# Mosfet_Driver_Circuit.net
KiCad netlist of a schematic drawn in Altium Designer
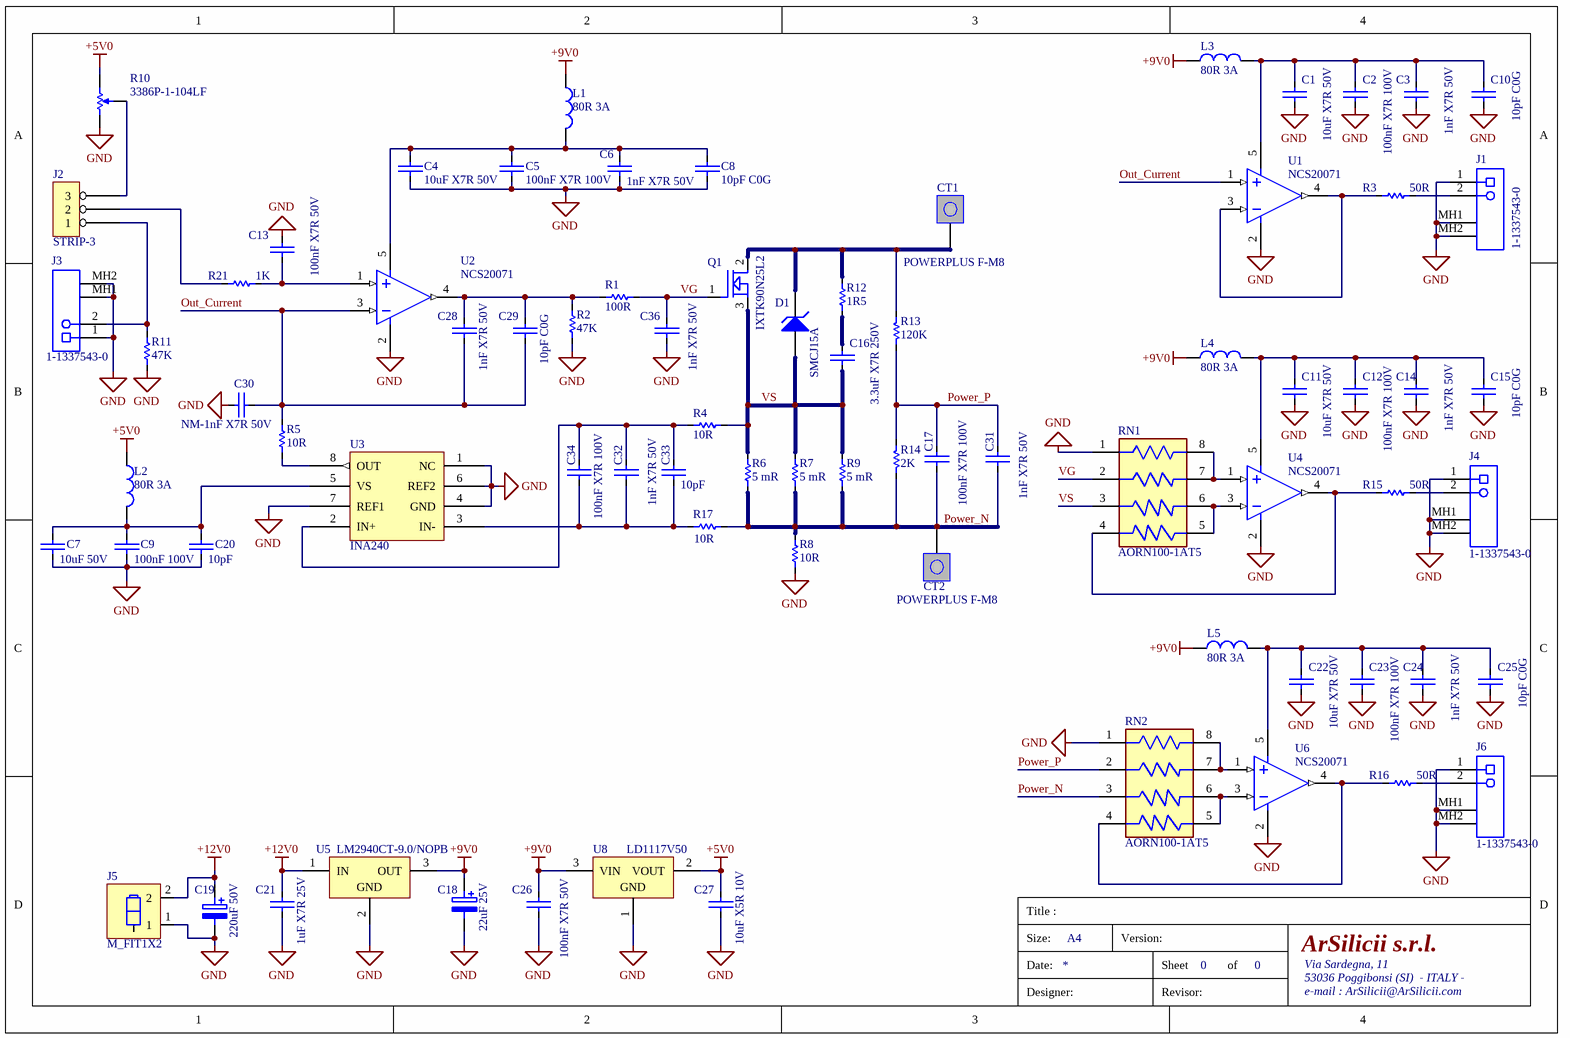
[diagram p0: Mosfet_Driver_Circuit.SchDoc]

(export (version "E")
  (design (tool "Eeschema 10.0.6"))
  (components
    (comp (ref "C1")
      (value "10uF X7R 50V")
      (footprint "1206")
      (description "Capacità")
      (fields
        (field (name "1 SUPPLIER PART NUMBER") "CL31B106KBHNNNE")
        (field (name "ARSILICII PART NUMBER") "CPC0232011")
      )
      (libsource (lib "Library_20-02-20") (part "CAP_10uF X7R 50V_1206"))
    )
    (comp (ref "C2")
      (value "100nF X7R 100V")
      (footprint "0805")
      (description "Capacità")
      (fields
        (field (name "1 SUPPLIER PART NUMBER") "CL21B104KCFSFNG")
        (field (name "2 SUPPLIER PART NUMBER") "1907331")
      )
      (libsource (lib "Library_20-02-20") (part "CAP_100nF X7R 100V_0805"))
    )
    (comp (ref "C3")
      (value "1nF X7R 50V")
      (footprint "0805")
      (description "Capacità")
      (fields
        (field (name "1 SUPPLIER PART NUMBER") "B37941K5102K60")
        (field (name "2 SUPPLIER PART NUMBER") "0805B102K5CT")
      )
      (libsource (lib "Library_20-02-20") (part "CAP_1nF X7R 50V_0805"))
    )
    (comp (ref "C4")
      (value "10uF X7R 50V")
      (footprint "1206")
      (description "Capacità")
      (fields
        (field (name "1 SUPPLIER PART NUMBER") "CL31B106KBHNNNE")
        (field (name "ARSILICII PART NUMBER") "CPC0232011")
      )
      (libsource (lib "Library_20-02-20") (part "CAP_10uF X7R 50V_1206"))
    )
    (comp (ref "C5")
      (value "100nF X7R 100V")
      (footprint "0805")
      (description "Capacità")
      (fields
        (field (name "1 SUPPLIER PART NUMBER") "CL21B104KCFSFNG")
        (field (name "2 SUPPLIER PART NUMBER") "1907331")
      )
      (libsource (lib "Library_20-02-20") (part "CAP_100nF X7R 100V_0805"))
    )
    (comp (ref "C6")
      (value "1nF X7R 50V")
      (footprint "0805")
      (description "Capacità")
      (fields
        (field (name "1 SUPPLIER PART NUMBER") "B37941K5102K60")
        (field (name "2 SUPPLIER PART NUMBER") "0805B102K5CT")
      )
      (libsource (lib "Library_20-02-20") (part "CAP_1nF X7R 50V_0805"))
    )
    (comp (ref "C7")
      (value "10uF 50V")
      (footprint "1206")
      (description "Capacità")
      (fields
        (field (name "1 SUPPLIER PART NUMBER") "CL31B106KBHNNNE")
        (field (name "ARSILICII PART NUMBER") "CPC0232011")
      )
      (libsource (lib "Library_20-02-20") (part "CAP_10uF X7R 50V_1206"))
    )
    (comp (ref "C8")
      (value "10pF C0G")
      (footprint "0805")
      (description "Capacità")
      (fields (field (name "ARSILICII PART NUMBER") "CPC0614010"))
      (libsource (lib "Library_20-02-20") (part "CAP_10pF C0G_0805"))
    )
    (comp (ref "C9")
      (value "100nF 100V")
      (footprint "0805")
      (description "Capacità")
      (fields
        (field (name "1 SUPPLIER PART NUMBER") "CL21B104KCFSFNG")
        (field (name "2 SUPPLIER PART NUMBER") "1907331")
      )
      (libsource (lib "Library_20-02-20") (part "CAP_100nF X7R 100V_0805"))
    )
    (comp (ref "C10")
      (value "10pF C0G")
      (footprint "0805")
      (description "Capacità")
      (fields (field (name "ARSILICII PART NUMBER") "CPC0614010"))
      (libsource (lib "Library_20-02-20") (part "CAP_10pF C0G_0805"))
    )
    (comp (ref "C11")
      (value "10uF X7R 50V")
      (footprint "1206")
      (description "Capacità")
      (fields
        (field (name "1 SUPPLIER PART NUMBER") "CL31B106KBHNNNE")
        (field (name "ARSILICII PART NUMBER") "CPC0232011")
      )
      (libsource (lib "Library_20-02-20") (part "CAP_10uF X7R 50V_1206"))
    )
    (comp (ref "C12")
      (value "100nF X7R 100V")
      (footprint "0805")
      (description "Capacità")
      (fields
        (field (name "1 SUPPLIER PART NUMBER") "CL21B104KCFSFNG")
        (field (name "2 SUPPLIER PART NUMBER") "1907331")
      )
      (libsource (lib "Library_20-02-20") (part "CAP_100nF X7R 100V_0805"))
    )
    (comp (ref "C13")
      (value "100nF X7R 50V")
      (footprint "0805")
      (description "Capacità")
      (fields
        (field (name "1 SUPPLIER PART NUMBER") "C0805C104K5RAC7800")
        (field (name "2 SUPPLIER PART NUMBER") "08055C104KAT2A AVX")
      )
      (libsource (lib "Library_20-02-20") (part "CAP_100nF X7R 50V_0805"))
    )
    (comp (ref "C14")
      (value "1nF X7R 50V")
      (footprint "0805")
      (description "Capacità")
      (fields
        (field (name "1 SUPPLIER PART NUMBER") "B37941K5102K60")
        (field (name "2 SUPPLIER PART NUMBER") "0805B102K5CT")
      )
      (libsource (lib "Library_20-02-20") (part "CAP_1nF X7R 50V_0805"))
    )
    (comp (ref "C15")
      (value "10pF C0G")
      (footprint "0805")
      (description "Capacità")
      (fields (field (name "ARSILICII PART NUMBER") "CPC0614010"))
      (libsource (lib "Library_20-02-20") (part "CAP_10pF C0G_0805"))
    )
    (comp (ref "C16")
      (value "3.3uF X7R 250V")
      (footprint "2220")
      (description "Capacità")
      (fields
        (field (name "1 SUPPLIER PART NUMBER") "2435506")
        (field (name "2 SUPPLIER PART NUMBER") "810-CGA9N3X7R2E105K")
      )
      (libsource (lib "Library_20-02-20") (part "CAP_1uF X7R 250V_2220"))
    )
    (comp (ref "C17")
      (value "100nF X7R 100V")
      (footprint "0805")
      (description "Capacità")
      (fields
        (field (name "1 SUPPLIER PART NUMBER") "CL21B104KCFSFNG")
        (field (name "2 SUPPLIER PART NUMBER") "1907331")
      )
      (libsource (lib "Library_20-02-20") (part "CAP_100nF X7R 100V_0805"))
    )
    (comp (ref "C18")
      (value "22uF 25V")
      (footprint "TANT_D")
      (description "Capacità polarizzata")
      (fields
        (field (name "1 SUPPLIER PART NUMBER") "KETT491D226K025AT")
        (field (name "ARSILICII PART NUMBER") "CPC0352022")
      )
      (libsource (lib "Library_20-02-20") (part "CAP_TANT_22uF 25V Case D"))
    )
    (comp (ref "C19")
      (value "220uF 50V")
      (footprint "C_G55")
      (description "Capacità polarizzata")
      (fields
        (field (name "2 SUPPLIER PART NUMBER") "5194346")
        (field (name "ARSILICII PART NUMBER") "CPC0402221")
      )
      (libsource (lib "Library_20-02-20") (part "CAP_EL_220uF 50V"))
    )
    (comp (ref "C20")
      (value "10pF")
      (footprint "0805")
      (description "Capacità")
      (fields (field (name "ARSILICII PART NUMBER") "CPC0614010"))
      (libsource (lib "Library_20-02-20") (part "CAP_10pF C0G_0805"))
    )
    (comp (ref "C21")
      (value "1uF X7R 25V")
      (footprint "0805")
      (description "Capacità")
      (fields
        (field (name "1 SUPPLIER PART NUMBER") "CL21B105KAFNNNG")
        (field (name "ARSILICII PART NUMBER") "CPC0212002")
      )
      (libsource (lib "Library_20-02-20") (part "CAP_1uF X7R 25V_0805"))
    )
    (comp (ref "C22")
      (value "10uF X7R 50V")
      (footprint "1206")
      (description "Capacità")
      (fields
        (field (name "1 SUPPLIER PART NUMBER") "CL31B106KBHNNNE")
        (field (name "ARSILICII PART NUMBER") "CPC0232011")
      )
      (libsource (lib "Library_20-02-20") (part "CAP_10uF X7R 50V_1206"))
    )
    (comp (ref "C23")
      (value "100nF X7R 100V")
      (footprint "0805")
      (description "Capacità")
      (fields
        (field (name "1 SUPPLIER PART NUMBER") "CL21B104KCFSFNG")
        (field (name "2 SUPPLIER PART NUMBER") "1907331")
      )
      (libsource (lib "Library_20-02-20") (part "CAP_100nF X7R 100V_0805"))
    )
    (comp (ref "C24")
      (value "1nF X7R 50V")
      (footprint "0805")
      (description "Capacità")
      (fields
        (field (name "1 SUPPLIER PART NUMBER") "B37941K5102K60")
        (field (name "2 SUPPLIER PART NUMBER") "0805B102K5CT")
      )
      (libsource (lib "Library_20-02-20") (part "CAP_1nF X7R 50V_0805"))
    )
    (comp (ref "C25")
      (value "10pF C0G")
      (footprint "0805")
      (description "Capacità")
      (fields (field (name "ARSILICII PART NUMBER") "CPC0614010"))
      (libsource (lib "Library_20-02-20") (part "CAP_10pF C0G_0805"))
    )
    (comp (ref "C26")
      (value "100nF X7R 50V")
      (footprint "0805")
      (description "Capacità")
      (fields
        (field (name "1 SUPPLIER PART NUMBER") "C0805C104K5RAC7800")
        (field (name "2 SUPPLIER PART NUMBER") "08055C104KAT2A AVX")
      )
      (libsource (lib "Library_20-02-20") (part "CAP_100nF X7R 50V_0805"))
    )
    (comp (ref "C27")
      (value "10uF X5R 10V")
      (footprint "0805")
      (description "Capacità")
      (fields
        (field (name "1 SUPPLIER PART NUMBER") "CL21A106KPFNNNE")
        (field (name "ARSILICII PART NUMBER") "CPC0212010")
      )
      (libsource (lib "Library_20-02-20") (part "CAP_10uF X5R 10V_0805"))
    )
    (comp (ref "C28")
      (value "1nF X7R 50V")
      (footprint "0805")
      (description "Capacità")
      (fields
        (field (name "1 SUPPLIER PART NUMBER") "B37941K5102K60")
        (field (name "2 SUPPLIER PART NUMBER") "0805B102K5CT")
      )
      (libsource (lib "Library_20-02-20") (part "CAP_1nF X7R 50V_0805"))
    )
    (comp (ref "C29")
      (value "10pF C0G")
      (footprint "0805")
      (description "Capacità")
      (fields (field (name "ARSILICII PART NUMBER") "CPC0614010"))
      (libsource (lib "Library_20-02-20") (part "CAP_10pF C0G_0805"))
    )
    (comp (ref "C30")
      (value "NM-1nF X7R 50V")
      (footprint "0805")
      (description "Capacità")
      (fields
        (field (name "1 SUPPLIER PART NUMBER") "B37941K5102K60")
        (field (name "2 SUPPLIER PART NUMBER") "0805B102K5CT")
      )
      (libsource (lib "Library_20-02-20") (part "CAP_1nF X7R 50V_0805"))
    )
    (comp (ref "C31")
      (value "1nF X7R 50V")
      (footprint "0805")
      (description "Capacità")
      (fields
        (field (name "1 SUPPLIER PART NUMBER") "B37941K5102K60")
        (field (name "2 SUPPLIER PART NUMBER") "0805B102K5CT")
      )
      (libsource (lib "Library_20-02-20") (part "CAP_1nF X7R 50V_0805"))
    )
    (comp (ref "C32")
      (value "1nF X7R 50V")
      (footprint "0805")
      (description "Capacità")
      (fields
        (field (name "1 SUPPLIER PART NUMBER") "B37941K5102K60")
        (field (name "2 SUPPLIER PART NUMBER") "0805B102K5CT")
      )
      (libsource (lib "Library_20-02-20") (part "CAP_1nF X7R 50V_0805"))
    )
    (comp (ref "C33")
      (value "10pF")
      (footprint "0805")
      (description "Capacità")
      (fields (field (name "ARSILICII PART NUMBER") "CPC0614010"))
      (libsource (lib "Library_20-02-20") (part "CAP_10pF C0G_0805"))
    )
    (comp (ref "C34")
      (value "100nF X7R 100V")
      (footprint "0805")
      (description "Capacità")
      (fields
        (field (name "1 SUPPLIER PART NUMBER") "CL21B104KCFSFNG")
        (field (name "2 SUPPLIER PART NUMBER") "1907331")
      )
      (libsource (lib "ArS_Library") (part "CAP_100nF X7R 100V_0805"))
    )
    (comp (ref "C36")
      (value "1nF X7R 50V")
      (footprint "0805")
      (description "Capacità")
      (fields
        (field (name "1 SUPPLIER PART NUMBER") "B37941K5102K60")
        (field (name "2 SUPPLIER PART NUMBER") "0805B102K5CT")
      )
      (libsource (lib "Library_20-02-20") (part "CAP_1nF X7R 50V_0805"))
    )
    (comp (ref "CT1")
      (value "POWERPLUS F-M8")
      (footprint "PowerPlus M8")
      (description "Singolo contatto")
      (fields
        (field (name "1 SUPPLIER PART NUMBER") "S98978")
        (field (name "ARSILICII PART NUMBER") "QC04000180")
      )
      (libsource (lib "Library_20-02-20") (part "PAD_POWERPLUS F-M8"))
    )
    (comp (ref "CT2")
      (value "POWERPLUS F-M8")
      (footprint "PowerPlus M8")
      (description "Singolo contatto")
      (fields
        (field (name "1 SUPPLIER PART NUMBER") "S98978")
        (field (name "ARSILICII PART NUMBER") "QC04000180")
      )
      (libsource (lib "") (part "PAD_POWERPLUS F-M8_1"))
    )
    (comp (ref "D1")
      (value "SMCJ15A")
      (footprint "LFUS-DO-214AB-2_V")
      (fields (field (name "MANUFACTURER") "Littelfuse"))
      (libsource (lib "Altium Content Vault") (part "DZEN-AK-2"))
    )
    (comp (ref "J1")
      (value "1-1337543-0")
      (footprint "TECO-1-1337543-0_V")
      (fields (field (name "MANUFACTURER") "TE Connectivity"))
      (libsource (lib "Altium Content Vault") (part "CN-1P-F-R2_A"))
    )
    (comp (ref "J2")
      (value "STRIP-3")
      (footprint "SIP-3")
      (libsource (lib "Library_20-02-20") (part "HEADER 3"))
    )
    (comp (ref "J3")
      (value "1-1337543-0")
      (footprint "TECO-1-1337543-0_V")
      (fields (field (name "MANUFACTURER") "TE Connectivity"))
      (libsource (lib "") (part "CN-1P-F-R2_A_1"))
    )
    (comp (ref "J4")
      (value "1-1337543-0")
      (footprint "TECO-1-1337543-0_V")
      (fields (field (name "MANUFACTURER") "TE Connectivity"))
      (libsource (lib "Altium Content Vault") (part "CN-1P-F-R2_A"))
    )
    (comp (ref "J5")
      (value "M_FIT1X2")
      (footprint "M_FIT_JR1X2V")
      (description "Mini Fit Junior 2 poli")
      (fields (field (name "ARSILICII PART NUMBER") "QA02006000") (field (name "MANUFACTURER") "Molex"))
      (libsource (lib "Library_20-02-20") (part "M_FIT1X2"))
    )
    (comp (ref "J6")
      (value "1-1337543-0")
      (footprint "TECO-1-1337543-0_V")
      (fields (field (name "MANUFACTURER") "TE Connectivity"))
      (libsource (lib "Altium Content Vault") (part "CN-1P-F-R2_A"))
    )
    (comp (ref "L1")
      (value "80R 3A")
      (footprint "1206")
      (description "Ferrite")
      (fields
        (field (name "1 SUPPLIER PART NUMBER") "3275550P")
        (field (name "ARSILICII PART NUMBER") "CPF0006000")
      )
      (libsource (lib "Library_20-02-20") (part "Ferrite 80R 3A"))
    )
    (comp (ref "L2")
      (value "80R 3A")
      (footprint "1206")
      (description "Ferrite")
      (fields
        (field (name "1 SUPPLIER PART NUMBER") "3275550P")
        (field (name "ARSILICII PART NUMBER") "CPF0006000")
      )
      (libsource (lib "Library_20-02-20") (part "Ferrite 80R 3A"))
    )
    (comp (ref "L3")
      (value "80R 3A")
      (footprint "1206")
      (description "Ferrite")
      (fields
        (field (name "1 SUPPLIER PART NUMBER") "3275550P")
        (field (name "ARSILICII PART NUMBER") "CPF0006000")
      )
      (libsource (lib "Library_20-02-20") (part "Ferrite 80R 3A"))
    )
    (comp (ref "L4")
      (value "80R 3A")
      (footprint "1206")
      (description "Ferrite")
      (fields
        (field (name "1 SUPPLIER PART NUMBER") "3275550P")
        (field (name "ARSILICII PART NUMBER") "CPF0006000")
      )
      (libsource (lib "Library_20-02-20") (part "Ferrite 80R 3A"))
    )
    (comp (ref "L5")
      (value "80R 3A")
      (footprint "1206")
      (description "Ferrite")
      (fields
        (field (name "1 SUPPLIER PART NUMBER") "3275550P")
        (field (name "ARSILICII PART NUMBER") "CPF0006000")
      )
      (libsource (lib "Library_20-02-20") (part "Ferrite 80R 3A"))
    )
    (comp (ref "Q1")
      (value "IXTK90N25L2")
      (footprint "Library_20-02-20:TO-247")
      (description "MOS CANALE N-250V-90A Linear")
      (fields
        (field (name "1 SUPPLIER PART NUMBER") "PB90N06S4-04")
        (field (name "2 SUPPLIER PART NUMBER") "826-9042P")
      )
      (libsource (lib "Library_20-02-20") (part "IXTK90N25L2"))
    )
    (comp (ref "R1")
      (value "100R")
      (footprint "0805")
      (description "Resistenza")
      (libsource (lib "Library_20-02-20") (part "RES_SMD"))
    )
    (comp (ref "R2")
      (value "47K")
      (footprint "0805")
      (description "Resistenza")
      (libsource (lib "Library_20-02-20") (part "RES_SMD"))
    )
    (comp (ref "R3")
      (value "50R")
      (footprint "0805")
      (description "Resistenza")
      (libsource (lib "Library_20-02-20") (part "RES_SMD"))
    )
    (comp (ref "R4")
      (value "10R")
      (footprint "0805")
      (description "Resistenza")
      (libsource (lib "Library_20-02-20") (part "RES_SMD"))
    )
    (comp (ref "R5")
      (value "10R")
      (footprint "0805")
      (description "Resistenza")
      (libsource (lib "Library_20-02-20") (part "RES_SMD"))
    )
    (comp (ref "R6")
      (value "5 mR")
      (footprint "2512")
      (description "Resistenza")
      (libsource (lib "Library_20-02-20") (part "RES_SMD"))
    )
    (comp (ref "R7")
      (value "5 mR")
      (footprint "2512")
      (description "Resistenza")
      (libsource (lib "Library_20-02-20") (part "RES_SMD"))
    )
    (comp (ref "R8")
      (value "10R")
      (footprint "1206")
      (description "Resistenza")
      (libsource (lib "Library_20-02-20") (part "RES_SMD"))
    )
    (comp (ref "R9")
      (value "5 mR")
      (footprint "2512")
      (description "Resistenza")
      (libsource (lib "Library_20-02-20") (part "RES_SMD"))
    )
    (comp (ref "R10")
      (value "3386P-1-104LF")
      (footprint "BOUR-3386P")
      (fields (field (name "TOLERANCE") "10%") (field (name "MANUFACTURER") "Bourns"))
      (libsource (lib "Altium Content Vault") (part "RES-ADJ-3_A"))
    )
    (comp (ref "R11")
      (value "47K")
      (footprint "0805")
      (description "Resistenza")
      (libsource (lib "Library_20-02-20") (part "RES_SMD"))
    )
    (comp (ref "R12")
      (value "1R5")
      (footprint "2512")
      (description "Resistenza")
      (libsource (lib "Library_20-02-20") (part "RES_SMD"))
    )
    (comp (ref "R13")
      (value "120K")
      (footprint "2512")
      (description "Resistenza")
      (libsource (lib "Library_20-02-20") (part "RES_SMD"))
    )
    (comp (ref "R14")
      (value "2K")
      (footprint "2512")
      (description "Resistenza")
      (libsource (lib "Library_20-02-20") (part "RES_SMD"))
    )
    (comp (ref "R15")
      (value "50R")
      (footprint "0805")
      (description "Resistenza")
      (libsource (lib "Library_20-02-20") (part "RES_SMD"))
    )
    (comp (ref "R16")
      (value "50R")
      (footprint "0805")
      (description "Resistenza")
      (libsource (lib "Library_20-02-20") (part "RES_SMD"))
    )
    (comp (ref "R17")
      (value "10R")
      (footprint "0805")
      (description "Resistenza")
      (libsource (lib "Library_20-02-20") (part "RES_SMD"))
    )
    (comp (ref "R21")
      (value "1K")
      (footprint "0805")
      (description "Resistenza")
      (libsource (lib "Library_20-02-20") (part "RES_SMD"))
    )
    (comp (ref "RN1")
      (value "AORN100-1AT5")
      (footprint "FP-AORN100-1AT5-IPC_C")
      (description "RES NETWORK 4 RES MULT OHM 8SOIC")
      (fields (field (name "MANUFACTURER") "Vishay") (field (name "TOLERANCE") "0.1%"))
      (libsource (lib "Altium Content Vault") (part "8441eaa576eb2593bca60d5301712c1"))
    )
    (comp (ref "RN2")
      (value "AORN100-1AT5")
      (footprint "FP-AORN100-1AT5-IPC_C")
      (description "RES NETWORK 4 RES MULT OHM 8SOIC")
      (fields (field (name "MANUFACTURER") "Vishay") (field (name "TOLERANCE") "0.1%"))
      (libsource (lib "Altium Content Vault") (part "8441eaa576eb2593bca60d5301712c1"))
    )
    (comp (ref "U1")
      (value "NCS20071")
      (footprint "SOT-553-5")
      (description "Rail-to-Rail Input/Output, 3 MHz Op Amps")
      (fields
        (field (name "1 SUPPLIER PART NUMBER") "MCP6021-E/SN-ND")
        (field (name "MANUFACTURER") "Microchip Technology")
      )
      (libsource (lib "Library_20-02-20") (part "NCS20071"))
    )
    (comp (ref "U2")
      (value "NCS20071")
      (footprint "SOT-553-5")
      (description "Rail-to-Rail Input/Output, 3 MHz Op Amps")
      (fields
        (field (name "1 SUPPLIER PART NUMBER") "MCP6021-E/SN-ND")
        (field (name "MANUFACTURER") "Microchip Technology")
      )
      (libsource (lib "Library_20-02-20") (part "NCS20071"))
    )
    (comp (ref "U3")
      (value "INA240")
      (footprint "TSSOP-8")
      (description "Current sense amplifier")
      (libsource (lib "Library_20-02-20") (part "INA240"))
    )
    (comp (ref "U4")
      (value "NCS20071")
      (footprint "SOT-553-5")
      (description "Rail-to-Rail Input/Output, 3 MHz Op Amps")
      (fields
        (field (name "1 SUPPLIER PART NUMBER") "MCP6021-E/SN-ND")
        (field (name "MANUFACTURER") "Microchip Technology")
      )
      (libsource (lib "Library_20-02-20") (part "NCS20071"))
    )
    (comp (ref "U5")
      (value "LM2940CT-9.0/NOPB")
      (footprint "NDE0003A")
      (description "1A Low Dropout Regulator, 3-pin TO-220, Pb-Free")
      (fields (field (name "MANUFACTURER") "Texas Instruments"))
      (libsource (lib "Altium Content Vault") (part "PM-REG-LM2940-SIL3"))
    )
    (comp (ref "U6")
      (value "NCS20071")
      (footprint "SOT-553-5")
      (description "Rail-to-Rail Input/Output, 3 MHz Op Amps")
      (fields
        (field (name "1 SUPPLIER PART NUMBER") "MCP6021-E/SN-ND")
        (field (name "MANUFACTURER") "Microchip Technology")
      )
      (libsource (lib "Library_20-02-20") (part "NCS20071"))
    )
    (comp (ref "U8")
      (value "LD1117V50")
      (footprint "TO220")
      (description "Fixed Low Drop Positive Voltage Regulator, 5V, 3-Pin TO-220")
      (libsource (lib "Altium Content Vault") (part "PM-REG-LD1117V-SIL3"))
    )
  )
  (nets
    (net (code "1") (name "+5V0") (class "Default")
      (node (ref "C27") (pin "1") (pintype "passive"))
      (node (ref "L2") (pin "1") (pinfunction "1_1") (pintype "passive"))
      (node (ref "R10") (pin "3") (pinfunction "3_3") (pintype "passive"))
      (node (ref "U8") (pin "2") (pinfunction "VOUT_2") (pintype "power_in"))
    )
    (net (code "2") (name "+9V0") (class "Default")
      (node (ref "C18") (pin "1") (pintype "passive"))
      (node (ref "C26") (pin "1") (pintype "passive"))
      (node (ref "L1") (pin "1") (pinfunction "1_1") (pintype "passive"))
      (node (ref "L3") (pin "1") (pinfunction "1_1") (pintype "passive"))
      (node (ref "L4") (pin "1") (pinfunction "1_1") (pintype "passive"))
      (node (ref "L5") (pin "1") (pinfunction "1_1") (pintype "passive"))
      (node (ref "U5") (pin "3") (pinfunction "OUT_3") (pintype "power_in"))
      (node (ref "U8") (pin "3") (pinfunction "VIN_3") (pintype "power_in"))
    )
    (net (code "3") (name "+12V0") (class "Default")
      (node (ref "C19") (pin "1") (pintype "passive"))
      (node (ref "C21") (pin "1") (pintype "passive"))
      (node (ref "J5") (pin "2") (pinfunction "2_2") (pintype "passive"))
      (node (ref "U5") (pin "1") (pinfunction "IN_1") (pintype "power_in"))
    )
    (net (code "4") (name "/Out_Current") (class "Default")
      (node (ref "C28") (pin "2") (pintype "passive"))
      (node (ref "C29") (pin "2") (pintype "passive"))
      (node (ref "C30") (pin "2") (pintype "passive"))
      (node (ref "R5") (pin "2") (pinfunction "2_2") (pintype "passive"))
      (node (ref "U1") (pin "1") (pintype "input"))
      (node (ref "U2") (pin "3") (pintype "input"))
    )
    (net (code "5") (name "/Power_N") (class "Default")
      (node (ref "C17") (pin "2") (pintype "passive"))
      (node (ref "C31") (pin "2") (pintype "passive"))
      (node (ref "CT2") (pin "1") (pinfunction "1_1") (pintype "passive"))
      (node (ref "R14") (pin "2") (pinfunction "2_2") (pintype "passive"))
      (node (ref "R17") (pin "2") (pinfunction "2_2") (pintype "passive"))
      (node (ref "R6") (pin "2") (pinfunction "2_2") (pintype "passive"))
      (node (ref "R7") (pin "2") (pinfunction "2_2") (pintype "passive"))
      (node (ref "R8") (pin "1") (pinfunction "1_1") (pintype "passive"))
      (node (ref "R9") (pin "2") (pinfunction "2_2") (pintype "passive"))
      (node (ref "RN2") (pin "3") (pinfunction "3_3") (pintype "passive"))
    )
    (net (code "6") (name "/Power_P") (class "Default")
      (node (ref "C17") (pin "1") (pintype "passive"))
      (node (ref "C31") (pin "1") (pintype "passive"))
      (node (ref "R13") (pin "2") (pinfunction "2_2") (pintype "passive"))
      (node (ref "R14") (pin "1") (pinfunction "1_1") (pintype "passive"))
      (node (ref "RN2") (pin "2") (pinfunction "2_2") (pintype "passive"))
    )
    (net (code "7") (name "/VG") (class "Default")
      (node (ref "C36") (pin "1") (pintype "passive"))
      (node (ref "Q1") (pin "1") (pinfunction "GATE_1") (pintype "passive"))
      (node (ref "R1") (pin "2") (pinfunction "2_2") (pintype "passive"))
      (node (ref "RN1") (pin "2") (pinfunction "2_2") (pintype "passive"))
    )
    (net (code "8") (name "/VS") (class "Default")
      (node (ref "C16") (pin "2") (pintype "passive"))
      (node (ref "D1") (pin "1") (pinfunction "A_1") (pintype "passive"))
      (node (ref "Q1") (pin "3") (pinfunction "SOURCE_3") (pintype "passive"))
      (node (ref "R4") (pin "2") (pinfunction "2_2") (pintype "passive"))
      (node (ref "R6") (pin "1") (pinfunction "1_1") (pintype "passive"))
      (node (ref "R7") (pin "1") (pinfunction "1_1") (pintype "passive"))
      (node (ref "R9") (pin "1") (pinfunction "1_1") (pintype "passive"))
      (node (ref "RN1") (pin "3") (pinfunction "3_3") (pintype "passive"))
    )
    (net (code "9") (name "GND") (class "Default")
      (node (ref "C1") (pin "2") (pintype "passive"))
      (node (ref "C10") (pin "2") (pintype "passive"))
      (node (ref "C11") (pin "2") (pintype "passive"))
      (node (ref "C12") (pin "2") (pintype "passive"))
      (node (ref "C13") (pin "1") (pintype "passive"))
      (node (ref "C14") (pin "2") (pintype "passive"))
      (node (ref "C15") (pin "2") (pintype "passive"))
      (node (ref "C18") (pin "2") (pintype "passive"))
      (node (ref "C19") (pin "2") (pintype "passive"))
      (node (ref "C2") (pin "2") (pintype "passive"))
      (node (ref "C20") (pin "2") (pintype "passive"))
      (node (ref "C21") (pin "2") (pintype "passive"))
      (node (ref "C22") (pin "2") (pintype "passive"))
      (node (ref "C23") (pin "2") (pintype "passive"))
      (node (ref "C24") (pin "2") (pintype "passive"))
      (node (ref "C25") (pin "2") (pintype "passive"))
      (node (ref "C26") (pin "2") (pintype "passive"))
      (node (ref "C27") (pin "2") (pintype "passive"))
      (node (ref "C3") (pin "2") (pintype "passive"))
      (node (ref "C30") (pin "1") (pintype "passive"))
      (node (ref "C36") (pin "2") (pintype "passive"))
      (node (ref "C4") (pin "2") (pintype "passive"))
      (node (ref "C5") (pin "2") (pintype "passive"))
      (node (ref "C6") (pin "2") (pintype "passive"))
      (node (ref "C7") (pin "2") (pintype "passive"))
      (node (ref "C8") (pin "2") (pintype "passive"))
      (node (ref "C9") (pin "2") (pintype "passive"))
      (node (ref "J1") (pin "1") (pinfunction "1_1") (pintype "passive"))
      (node (ref "J1") (pin "MH1") (pinfunction "MH1_MH1") (pintype "passive"))
      (node (ref "J1") (pin "MH2") (pinfunction "MH2_MH2") (pintype "passive"))
      (node (ref "J3") (pin "1") (pinfunction "1_1") (pintype "passive"))
      (node (ref "J3") (pin "MH1") (pinfunction "MH1_MH1") (pintype "passive"))
      (node (ref "J3") (pin "MH2") (pinfunction "MH2_MH2") (pintype "passive"))
      (node (ref "J4") (pin "1") (pinfunction "1_1") (pintype "passive"))
      (node (ref "J4") (pin "MH1") (pinfunction "MH1_MH1") (pintype "passive"))
      (node (ref "J4") (pin "MH2") (pinfunction "MH2_MH2") (pintype "passive"))
      (node (ref "J5") (pin "1") (pinfunction "1_1") (pintype "passive"))
      (node (ref "J6") (pin "1") (pinfunction "1_1") (pintype "passive"))
      (node (ref "J6") (pin "MH1") (pinfunction "MH1_MH1") (pintype "passive"))
      (node (ref "J6") (pin "MH2") (pinfunction "MH2_MH2") (pintype "passive"))
      (node (ref "R10") (pin "1") (pinfunction "1_1") (pintype "passive"))
      (node (ref "R11") (pin "1") (pinfunction "1_1") (pintype "passive"))
      (node (ref "R2") (pin "2") (pinfunction "2_2") (pintype "passive"))
      (node (ref "R8") (pin "2") (pinfunction "2_2") (pintype "passive"))
      (node (ref "RN1") (pin "1") (pinfunction "1_1") (pintype "passive"))
      (node (ref "RN2") (pin "1") (pinfunction "1_1") (pintype "passive"))
      (node (ref "U1") (pin "2") (pintype "power_in"))
      (node (ref "U2") (pin "2") (pintype "power_in"))
      (node (ref "U3") (pin "1") (pinfunction "NC_1") (pintype "passive"))
      (node (ref "U3") (pin "4") (pinfunction "GND_4") (pintype "power_in"))
      (node (ref "U3") (pin "6") (pinfunction "REF2_6") (pintype "passive"))
      (node (ref "U3") (pin "7") (pinfunction "REF1_7") (pintype "passive"))
      (node (ref "U4") (pin "2") (pintype "power_in"))
      (node (ref "U5") (pin "2") (pinfunction "GND_2") (pintype "power_in"))
      (node (ref "U6") (pin "2") (pintype "power_in"))
      (node (ref "U8") (pin "1") (pinfunction "GND_1") (pintype "power_in"))
    )
    (net (code "10") (name "Net-(C1-Pad1)") (class "Default")
      (node (ref "C1") (pin "1") (pintype "passive"))
      (node (ref "C10") (pin "1") (pintype "passive"))
      (node (ref "C2") (pin "1") (pintype "passive"))
      (node (ref "C3") (pin "1") (pintype "passive"))
      (node (ref "L3") (pin "2") (pinfunction "2_2") (pintype "passive"))
      (node (ref "U1") (pin "5") (pintype "power_in"))
    )
    (net (code "11") (name "Net-(C4-Pad1)") (class "Default")
      (node (ref "C4") (pin "1") (pintype "passive"))
      (node (ref "C5") (pin "1") (pintype "passive"))
      (node (ref "C6") (pin "1") (pintype "passive"))
      (node (ref "C8") (pin "1") (pintype "passive"))
      (node (ref "L1") (pin "2") (pinfunction "2_2") (pintype "passive"))
      (node (ref "U2") (pin "5") (pintype "power_in"))
    )
    (net (code "12") (name "Net-(C11-Pad1)") (class "Default")
      (node (ref "C11") (pin "1") (pintype "passive"))
      (node (ref "C12") (pin "1") (pintype "passive"))
      (node (ref "C14") (pin "1") (pintype "passive"))
      (node (ref "C15") (pin "1") (pintype "passive"))
      (node (ref "L4") (pin "2") (pinfunction "2_2") (pintype "passive"))
      (node (ref "U4") (pin "5") (pintype "power_in"))
    )
    (net (code "13") (name "Net-(C13-Pad2)") (class "Default")
      (node (ref "C13") (pin "2") (pintype "passive"))
      (node (ref "R21") (pin "2") (pinfunction "2_2") (pintype "passive"))
      (node (ref "U2") (pin "1") (pintype "input"))
    )
    (net (code "14") (name "Net-(C16-Pad1)") (class "Default")
      (node (ref "C16") (pin "1") (pintype "passive"))
      (node (ref "R12") (pin "2") (pinfunction "2_2") (pintype "passive"))
    )
    (net (code "15") (name "Net-(C22-Pad1)") (class "Default")
      (node (ref "C22") (pin "1") (pintype "passive"))
      (node (ref "C23") (pin "1") (pintype "passive"))
      (node (ref "C24") (pin "1") (pintype "passive"))
      (node (ref "C25") (pin "1") (pintype "passive"))
      (node (ref "L5") (pin "2") (pinfunction "2_2") (pintype "passive"))
      (node (ref "U6") (pin "5") (pintype "power_in"))
    )
    (net (code "16") (name "Net-(C28-Pad1)") (class "Default")
      (node (ref "C28") (pin "1") (pintype "passive"))
      (node (ref "C29") (pin "1") (pintype "passive"))
      (node (ref "R1") (pin "1") (pinfunction "1_1") (pintype "passive"))
      (node (ref "R2") (pin "1") (pinfunction "1_1") (pintype "passive"))
      (node (ref "U2") (pin "4") (pintype "output"))
    )
    (net (code "17") (name "Net-(D1-K)") (class "Default")
      (node (ref "CT1") (pin "1") (pinfunction "1_1") (pintype "passive"))
      (node (ref "D1") (pin "2") (pinfunction "K_2") (pintype "passive"))
      (node (ref "Q1") (pin "2") (pinfunction "DRAIN_2") (pintype "passive"))
      (node (ref "R12") (pin "1") (pinfunction "1_1") (pintype "passive"))
      (node (ref "R13") (pin "1") (pinfunction "1_1") (pintype "passive"))
    )
    (net (code "18") (name "Net-(J1-Pad2)") (class "Default")
      (node (ref "J1") (pin "2") (pinfunction "2_2") (pintype "passive"))
      (node (ref "R3") (pin "1") (pinfunction "1_1") (pintype "passive"))
    )
    (net (code "19") (name "Net-(J2-Pad1)") (class "Default")
      (node (ref "J2") (pin "1") (pinfunction "1_1") (pintype "passive"))
      (node (ref "J3") (pin "2") (pinfunction "2_2") (pintype "passive"))
      (node (ref "R11") (pin "2") (pinfunction "2_2") (pintype "passive"))
    )
    (net (code "20") (name "Net-(J2-Pad2)") (class "Default")
      (node (ref "J2") (pin "2") (pinfunction "2_2") (pintype "passive"))
      (node (ref "R21") (pin "1") (pinfunction "1_1") (pintype "passive"))
    )
    (net (code "21") (name "Net-(J2-Pad3)") (class "Default")
      (node (ref "J2") (pin "3") (pinfunction "3_3") (pintype "passive"))
      (node (ref "R10") (pin "2") (pinfunction "2_2") (pintype "passive"))
    )
    (net (code "22") (name "Net-(J4-Pad2)") (class "Default")
      (node (ref "J4") (pin "2") (pinfunction "2_2") (pintype "passive"))
      (node (ref "R15") (pin "1") (pinfunction "1_1") (pintype "passive"))
    )
    (net (code "23") (name "Net-(J6-Pad2)") (class "Default")
      (node (ref "J6") (pin "2") (pinfunction "2_2") (pintype "passive"))
      (node (ref "R16") (pin "1") (pinfunction "1_1") (pintype "passive"))
    )
    (net (code "24") (name "Net-(R3-Pad2)") (class "Default")
      (node (ref "R3") (pin "2") (pinfunction "2_2") (pintype "passive"))
      (node (ref "U1") (pin "3") (pintype "input"))
      (node (ref "U1") (pin "4") (pintype "output"))
    )
    (net (code "25") (name "Net-(R15-Pad2)") (class "Default")
      (node (ref "R15") (pin "2") (pinfunction "2_2") (pintype "passive"))
      (node (ref "RN1") (pin "4") (pinfunction "4_4") (pintype "passive"))
      (node (ref "U4") (pin "4") (pintype "output"))
    )
    (net (code "26") (name "Net-(R16-Pad2)") (class "Default")
      (node (ref "R16") (pin "2") (pinfunction "2_2") (pintype "passive"))
      (node (ref "RN2") (pin "4") (pinfunction "4_4") (pintype "passive"))
      (node (ref "U6") (pin "4") (pintype "output"))
    )
    (net (code "27") (name "Net-(RN1-Pad5)") (class "Default")
      (node (ref "RN1") (pin "5") (pinfunction "5_5") (pintype "passive"))
      (node (ref "RN1") (pin "6") (pinfunction "6_6") (pintype "passive"))
      (node (ref "U4") (pin "3") (pintype "input"))
    )
    (net (code "28") (name "Net-(RN1-Pad7)") (class "Default")
      (node (ref "RN1") (pin "7") (pinfunction "7_7") (pintype "passive"))
      (node (ref "RN1") (pin "8") (pinfunction "8_8") (pintype "passive"))
      (node (ref "U4") (pin "1") (pintype "input"))
    )
    (net (code "29") (name "Net-(RN2-Pad5)") (class "Default")
      (node (ref "RN2") (pin "5") (pinfunction "5_5") (pintype "passive"))
      (node (ref "RN2") (pin "6") (pinfunction "6_6") (pintype "passive"))
      (node (ref "U6") (pin "3") (pintype "input"))
    )
    (net (code "30") (name "Net-(RN2-Pad7)") (class "Default")
      (node (ref "RN2") (pin "7") (pinfunction "7_7") (pintype "passive"))
      (node (ref "RN2") (pin "8") (pinfunction "8_8") (pintype "passive"))
      (node (ref "U6") (pin "1") (pintype "input"))
    )
    (net (code "31") (name "Net-(U3-IN+)") (class "Default")
      (node (ref "C32") (pin "1") (pintype "passive"))
      (node (ref "C33") (pin "1") (pintype "passive"))
      (node (ref "C34") (pin "1") (pintype "passive"))
      (node (ref "R4") (pin "1") (pinfunction "1_1") (pintype "passive"))
      (node (ref "U3") (pin "2") (pinfunction "IN+_2") (pintype "tri_state"))
    )
    (net (code "32") (name "Net-(U3-IN-)") (class "Default")
      (node (ref "C32") (pin "2") (pintype "passive"))
      (node (ref "C33") (pin "2") (pintype "passive"))
      (node (ref "C34") (pin "2") (pintype "passive"))
      (node (ref "R17") (pin "1") (pinfunction "1_1") (pintype "passive"))
      (node (ref "U3") (pin "3") (pinfunction "IN-_3") (pintype "tri_state"))
    )
    (net (code "33") (name "Net-(U3-OUT)") (class "Default")
      (node (ref "R5") (pin "1") (pinfunction "1_1") (pintype "passive"))
      (node (ref "U3") (pin "8") (pinfunction "OUT_8") (pintype "output"))
    )
    (net (code "34") (name "Net-(U3-VS)") (class "Default")
      (node (ref "C20") (pin "1") (pintype "passive"))
      (node (ref "C7") (pin "1") (pintype "passive"))
      (node (ref "C9") (pin "1") (pintype "passive"))
      (node (ref "L2") (pin "2") (pinfunction "2_2") (pintype "passive"))
      (node (ref "U3") (pin "5") (pinfunction "VS_5") (pintype "power_in"))
    )
  )
)
